# IDP_Shield.net
KiCad netlist of a schematic drawn in EAGLE
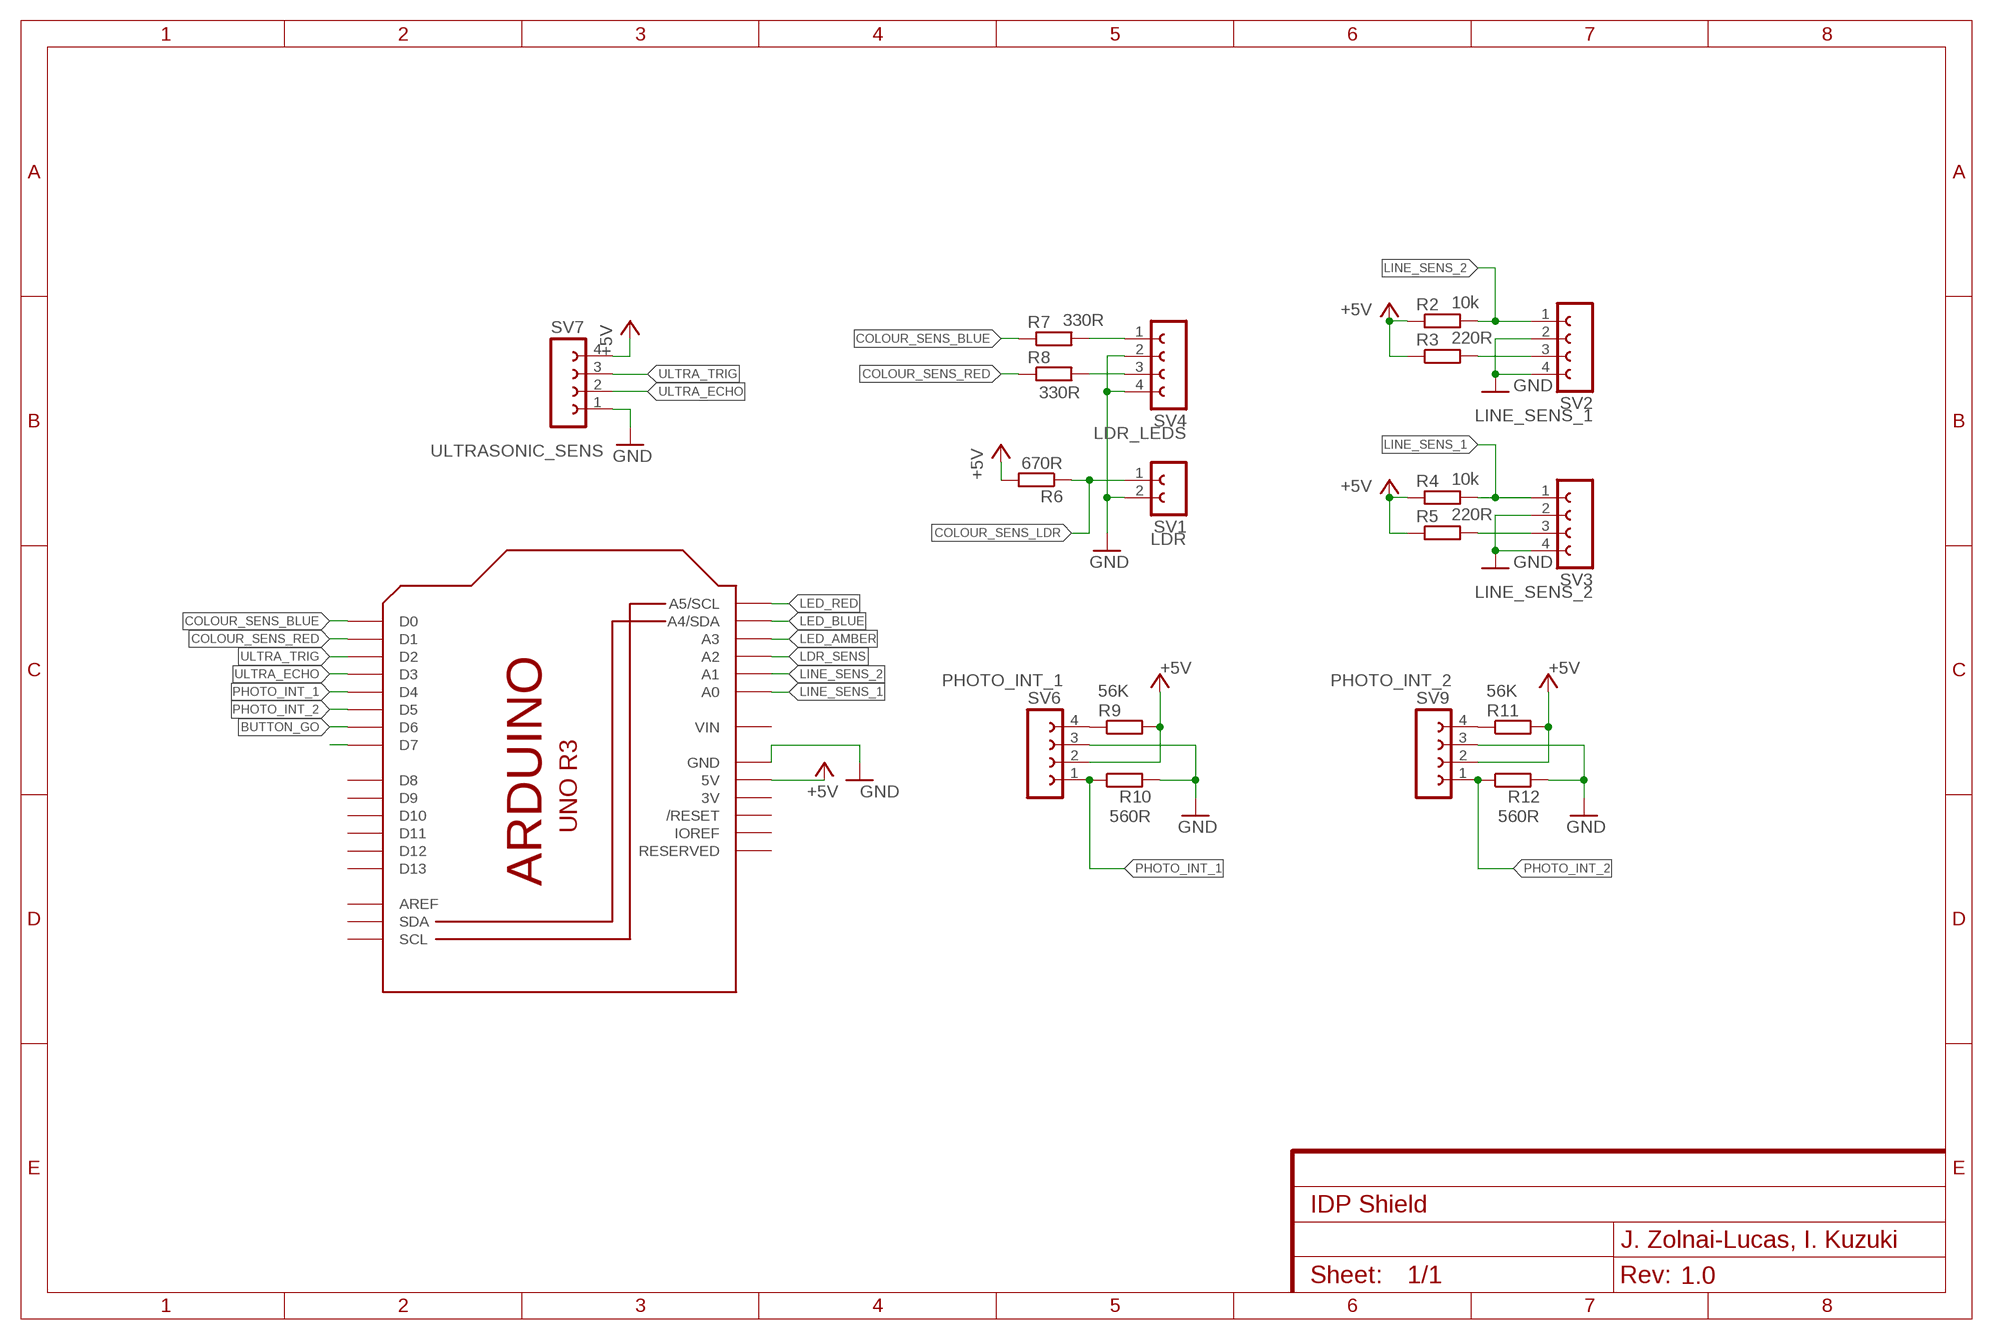
[diagram p0: schematic, sheet 1]

(export (version "E")
  (design (tool "Eeschema 10.0.6"))
  (components
    (comp (ref "M1")
      (value "IDP_PROTOBOARD")
      (footprint "eagle-import:IDP_PROTO")
      (libsource (lib "eagle-import") (part "IDP_PROTOBOARD"))
    )
    (comp (ref "R2")
      (value "10k")
      (footprint "eagle-import:0207_10")
      (libsource (lib "eagle-import") (part "R-EU_0207/10"))
    )
    (comp (ref "R3")
      (value "220R")
      (footprint "eagle-import:0207_10")
      (libsource (lib "eagle-import") (part "R-EU_0207/10"))
    )
    (comp (ref "R4")
      (value "10k")
      (footprint "eagle-import:0207_10")
      (libsource (lib "eagle-import") (part "R-EU_0207/10"))
    )
    (comp (ref "R5")
      (value "220R")
      (footprint "eagle-import:0207_10")
      (libsource (lib "eagle-import") (part "R-EU_0207/10"))
    )
    (comp (ref "R6")
      (value "670R")
      (footprint "eagle-import:0207_10")
      (libsource (lib "eagle-import") (part "R-EU_0207/10"))
    )
    (comp (ref "R7")
      (value "330R")
      (footprint "eagle-import:0207_10")
      (libsource (lib "eagle-import") (part "R-EU_0207/10"))
    )
    (comp (ref "R8")
      (value "330R")
      (footprint "eagle-import:0207_10")
      (libsource (lib "eagle-import") (part "R-EU_0207/10"))
    )
    (comp (ref "R9")
      (value "56K")
      (footprint "eagle-import:0207_10")
      (libsource (lib "eagle-import") (part "R-EU_0207/10"))
    )
    (comp (ref "R10")
      (value "560R")
      (footprint "eagle-import:0207_10")
      (libsource (lib "eagle-import") (part "R-EU_0207/10"))
    )
    (comp (ref "R11")
      (value "56K")
      (footprint "eagle-import:0207_10")
      (libsource (lib "eagle-import") (part "R-EU_0207/10"))
    )
    (comp (ref "R12")
      (value "560R")
      (footprint "eagle-import:0207_10")
      (libsource (lib "eagle-import") (part "R-EU_0207/10"))
    )
    (comp (ref "SV1")
      (value "LDR")
      (footprint "eagle-import:FE02-1")
      (libsource (lib "eagle-import") (part "FE02-1"))
    )
    (comp (ref "SV2")
      (value "LINE_SENS_1")
      (footprint "eagle-import:FE04-1")
      (libsource (lib "eagle-import") (part "FE04-1"))
    )
    (comp (ref "SV3")
      (value "LINE_SENS_2")
      (footprint "eagle-import:FE04-1")
      (libsource (lib "eagle-import") (part "FE04-1"))
    )
    (comp (ref "SV4")
      (value "LDR_LEDS")
      (footprint "eagle-import:FE04-1")
      (libsource (lib "eagle-import") (part "FE04-1"))
    )
    (comp (ref "SV6")
      (value "PHOTO_INT_1")
      (footprint "eagle-import:FE04-1")
      (libsource (lib "eagle-import") (part "FE04-1"))
    )
    (comp (ref "SV7")
      (value "ULTRASONIC_SENS")
      (footprint "eagle-import:FE04-1")
      (libsource (lib "eagle-import") (part "FE04-1"))
    )
    (comp (ref "SV9")
      (value "PHOTO_INT_2")
      (footprint "eagle-import:FE04-1")
      (libsource (lib "eagle-import") (part "FE04-1"))
    )
  )
  (nets
    (net (code "1") (name "+5V") (class "Default")
      (node (ref "M1") (pin "5V") (pinfunction "5V_5V") (pintype "power_in"))
      (node (ref "M1") (pin "5V@0") (pinfunction "5V_5V@0") (pintype "power_in"))
      (node (ref "M1") (pin "5V@1") (pinfunction "5V_5V@1") (pintype "power_in"))
      (node (ref "M1") (pin "5V@10") (pinfunction "5V_5V@10") (pintype "power_in"))
      (node (ref "M1") (pin "5V@11") (pinfunction "5V_5V@11") (pintype "power_in"))
      (node (ref "M1") (pin "5V@12") (pinfunction "5V_5V@12") (pintype "power_in"))
      (node (ref "M1") (pin "5V@13") (pinfunction "5V_5V@13") (pintype "power_in"))
      (node (ref "M1") (pin "5V@14") (pinfunction "5V_5V@14") (pintype "power_in"))
      (node (ref "M1") (pin "5V@15") (pinfunction "5V_5V@15") (pintype "power_in"))
      (node (ref "M1") (pin "5V@16") (pinfunction "5V_5V@16") (pintype "power_in"))
      (node (ref "M1") (pin "5V@17") (pinfunction "5V_5V@17") (pintype "power_in"))
      (node (ref "M1") (pin "5V@18") (pinfunction "5V_5V@18") (pintype "power_in"))
      (node (ref "M1") (pin "5V@19") (pinfunction "5V_5V@19") (pintype "power_in"))
      (node (ref "M1") (pin "5V@2") (pinfunction "5V_5V@2") (pintype "power_in"))
      (node (ref "M1") (pin "5V@20") (pinfunction "5V_5V@20") (pintype "power_in"))
      (node (ref "M1") (pin "5V@21") (pinfunction "5V_5V@21") (pintype "power_in"))
      (node (ref "M1") (pin "5V@22") (pinfunction "5V_5V@22") (pintype "power_in"))
      (node (ref "M1") (pin "5V@23") (pinfunction "5V_5V@23") (pintype "power_in"))
      (node (ref "M1") (pin "5V@24") (pinfunction "5V_5V@24") (pintype "power_in"))
      (node (ref "M1") (pin "5V@25") (pinfunction "5V_5V@25") (pintype "power_in"))
      (node (ref "M1") (pin "5V@26") (pinfunction "5V_5V@26") (pintype "power_in"))
      (node (ref "M1") (pin "5V@27") (pinfunction "5V_5V@27") (pintype "power_in"))
      (node (ref "M1") (pin "5V@28") (pinfunction "5V_5V@28") (pintype "power_in"))
      (node (ref "M1") (pin "5V@29") (pinfunction "5V_5V@29") (pintype "power_in"))
      (node (ref "M1") (pin "5V@3") (pinfunction "5V_5V@3") (pintype "power_in"))
      (node (ref "M1") (pin "5V@30") (pinfunction "5V_5V@30") (pintype "power_in"))
      (node (ref "M1") (pin "5V@31") (pinfunction "5V_5V@31") (pintype "power_in"))
      (node (ref "M1") (pin "5V@32") (pinfunction "5V_5V@32") (pintype "power_in"))
      (node (ref "M1") (pin "5V@33") (pinfunction "5V_5V@33") (pintype "power_in"))
      (node (ref "M1") (pin "5V@34") (pinfunction "5V_5V@34") (pintype "power_in"))
      (node (ref "M1") (pin "5V@35") (pinfunction "5V_5V@35") (pintype "power_in"))
      (node (ref "M1") (pin "5V@36") (pinfunction "5V_5V@36") (pintype "power_in"))
      (node (ref "M1") (pin "5V@37") (pinfunction "5V_5V@37") (pintype "power_in"))
      (node (ref "M1") (pin "5V@38") (pinfunction "5V_5V@38") (pintype "power_in"))
      (node (ref "M1") (pin "5V@39") (pinfunction "5V_5V@39") (pintype "power_in"))
      (node (ref "M1") (pin "5V@4") (pinfunction "5V_5V@4") (pintype "power_in"))
      (node (ref "M1") (pin "5V@40") (pinfunction "5V_5V@40") (pintype "power_in"))
      (node (ref "M1") (pin "5V@5") (pinfunction "5V_5V@5") (pintype "power_in"))
      (node (ref "M1") (pin "5V@6") (pinfunction "5V_5V@6") (pintype "power_in"))
      (node (ref "M1") (pin "5V@7") (pinfunction "5V_5V@7") (pintype "power_in"))
      (node (ref "M1") (pin "5V@8") (pinfunction "5V_5V@8") (pintype "power_in"))
      (node (ref "M1") (pin "5V@9") (pinfunction "5V_5V@9") (pintype "power_in"))
      (node (ref "R11") (pin "2") (pinfunction "2_2") (pintype "passive"))
      (node (ref "R2") (pin "1") (pinfunction "1_1") (pintype "passive"))
      (node (ref "R3") (pin "1") (pinfunction "1_1") (pintype "passive"))
      (node (ref "R4") (pin "1") (pinfunction "1_1") (pintype "passive"))
      (node (ref "R5") (pin "1") (pinfunction "1_1") (pintype "passive"))
      (node (ref "R6") (pin "2") (pinfunction "2_2") (pintype "passive"))
      (node (ref "R9") (pin "2") (pinfunction "2_2") (pintype "passive"))
      (node (ref "SV6") (pin "2") (pinfunction "2_2") (pintype "passive"))
      (node (ref "SV7") (pin "4") (pinfunction "4_4") (pintype "passive"))
      (node (ref "SV9") (pin "2") (pinfunction "2_2") (pintype "passive"))
    )
    (net (code "2") (name "/3V") (class "Default")
      (node (ref "M1") (pin "3V") (pinfunction "3V_3V") (pintype "power_in"))
    )
    (net (code "3") (name "BUTTON_GO") (class "Default")
      (node (ref "M1") (pin "D6") (pinfunction "D6_D6") (pintype "bidirectional"))
    )
    (net (code "4") (name "COLOUR_SENS_BLUE") (class "Default")
      (node (ref "M1") (pin "D0") (pinfunction "D0_D0") (pintype "bidirectional"))
      (node (ref "R7") (pin "1") (pinfunction "1_1") (pintype "passive"))
    )
    (net (code "5") (name "COLOUR_SENS_LDR") (class "Default")
      (node (ref "R6") (pin "1") (pinfunction "1_1") (pintype "passive"))
      (node (ref "SV1") (pin "1") (pinfunction "1_1") (pintype "passive"))
    )
    (net (code "6") (name "COLOUR_SENS_RED") (class "Default")
      (node (ref "M1") (pin "D1") (pinfunction "D1_D1") (pintype "bidirectional"))
      (node (ref "R8") (pin "1") (pinfunction "1_1") (pintype "passive"))
    )
    (net (code "7") (name "GND") (class "Default")
      (node (ref "M1") (pin "GND") (pinfunction "GND_GND") (pintype "power_in"))
      (node (ref "M1") (pin "GND16") (pinfunction "GND_GND16") (pintype "power_in"))
      (node (ref "M1") (pin "GND17") (pinfunction "GND_GND17") (pintype "power_in"))
      (node (ref "M1") (pin "GND18") (pinfunction "GND_GND18") (pintype "power_in"))
      (node (ref "M1") (pin "GND19") (pinfunction "GND_GND19") (pintype "power_in"))
      (node (ref "M1") (pin "GND20") (pinfunction "GND_GND20") (pintype "power_in"))
      (node (ref "M1") (pin "GND21") (pinfunction "GND_GND21") (pintype "power_in"))
      (node (ref "M1") (pin "GND22") (pinfunction "GND_GND22") (pintype "power_in"))
      (node (ref "M1") (pin "GND23") (pinfunction "GND_GND23") (pintype "power_in"))
      (node (ref "M1") (pin "GND24") (pinfunction "GND_GND24") (pintype "power_in"))
      (node (ref "M1") (pin "GND25") (pinfunction "GND_GND25") (pintype "power_in"))
      (node (ref "M1") (pin "GND@1") (pinfunction "GND_GND@1") (pintype "power_in"))
      (node (ref "M1") (pin "GND@10") (pinfunction "GND_GND@10") (pintype "power_in"))
      (node (ref "M1") (pin "GND@11") (pinfunction "GND_GND@11") (pintype "power_in"))
      (node (ref "M1") (pin "GND@12") (pinfunction "GND_GND@12") (pintype "power_in"))
      (node (ref "M1") (pin "GND@13") (pinfunction "GND_GND@13") (pintype "power_in"))
      (node (ref "M1") (pin "GND@14") (pinfunction "GND_GND@14") (pintype "power_in"))
      (node (ref "M1") (pin "GND@15") (pinfunction "GND_GND@15") (pintype "power_in"))
      (node (ref "M1") (pin "GND@2") (pinfunction "GND_GND@2") (pintype "power_in"))
      (node (ref "M1") (pin "GND@26") (pinfunction "GND_GND@26") (pintype "power_in"))
      (node (ref "M1") (pin "GND@27") (pinfunction "GND_GND@27") (pintype "power_in"))
      (node (ref "M1") (pin "GND@28") (pinfunction "GND_GND@28") (pintype "power_in"))
      (node (ref "M1") (pin "GND@29") (pinfunction "GND_GND@29") (pintype "power_in"))
      (node (ref "M1") (pin "GND@3") (pinfunction "GND_GND@3") (pintype "power_in"))
      (node (ref "M1") (pin "GND@30") (pinfunction "GND_GND@30") (pintype "power_in"))
      (node (ref "M1") (pin "GND@31") (pinfunction "GND_GND@31") (pintype "power_in"))
      (node (ref "M1") (pin "GND@32") (pinfunction "GND_GND@32") (pintype "power_in"))
      (node (ref "M1") (pin "GND@33") (pinfunction "GND_GND@33") (pintype "power_in"))
      (node (ref "M1") (pin "GND@34") (pinfunction "GND_GND@34") (pintype "power_in"))
      (node (ref "M1") (pin "GND@35") (pinfunction "GND_GND@35") (pintype "power_in"))
      (node (ref "M1") (pin "GND@36") (pinfunction "GND_GND@36") (pintype "power_in"))
      (node (ref "M1") (pin "GND@37") (pinfunction "GND_GND@37") (pintype "power_in"))
      (node (ref "M1") (pin "GND@38") (pinfunction "GND_GND@38") (pintype "power_in"))
      (node (ref "M1") (pin "GND@39") (pinfunction "GND_GND@39") (pintype "power_in"))
      (node (ref "M1") (pin "GND@4") (pinfunction "GND_GND@4") (pintype "power_in"))
      (node (ref "M1") (pin "GND@40") (pinfunction "GND_GND@40") (pintype "power_in"))
      (node (ref "M1") (pin "GND@41") (pinfunction "GND_GND@41") (pintype "power_in"))
      (node (ref "M1") (pin "GND@42") (pinfunction "GND_GND@42") (pintype "power_in"))
      (node (ref "M1") (pin "GND@43") (pinfunction "GND_GND@43") (pintype "power_in"))
      (node (ref "M1") (pin "GND@44") (pinfunction "GND_GND@44") (pintype "power_in"))
      (node (ref "M1") (pin "GND@45") (pinfunction "GND_GND@45") (pintype "power_in"))
      (node (ref "M1") (pin "GND@46") (pinfunction "GND_GND@46") (pintype "power_in"))
      (node (ref "M1") (pin "GND@47") (pinfunction "GND_GND@47") (pintype "power_in"))
      (node (ref "M1") (pin "GND@48") (pinfunction "GND_GND@48") (pintype "power_in"))
      (node (ref "M1") (pin "GND@5") (pinfunction "GND_GND@5") (pintype "power_in"))
      (node (ref "M1") (pin "GND@6") (pinfunction "GND_GND@6") (pintype "power_in"))
      (node (ref "M1") (pin "GND@7") (pinfunction "GND_GND@7") (pintype "power_in"))
      (node (ref "M1") (pin "GND@8") (pinfunction "GND_GND@8") (pintype "power_in"))
      (node (ref "M1") (pin "GND@9") (pinfunction "GND_GND@9") (pintype "power_in"))
      (node (ref "R10") (pin "2") (pinfunction "2_2") (pintype "passive"))
      (node (ref "R12") (pin "2") (pinfunction "2_2") (pintype "passive"))
      (node (ref "SV1") (pin "2") (pinfunction "2_2") (pintype "passive"))
      (node (ref "SV2") (pin "2") (pinfunction "2_2") (pintype "passive"))
      (node (ref "SV2") (pin "4") (pinfunction "4_4") (pintype "passive"))
      (node (ref "SV3") (pin "2") (pinfunction "2_2") (pintype "passive"))
      (node (ref "SV3") (pin "4") (pinfunction "4_4") (pintype "passive"))
      (node (ref "SV4") (pin "2") (pinfunction "2_2") (pintype "passive"))
      (node (ref "SV4") (pin "4") (pinfunction "4_4") (pintype "passive"))
      (node (ref "SV6") (pin "3") (pinfunction "3_3") (pintype "passive"))
      (node (ref "SV7") (pin "1") (pinfunction "1_1") (pintype "passive"))
      (node (ref "SV9") (pin "3") (pinfunction "3_3") (pintype "passive"))
    )
    (net (code "8") (name "LDR_SENS") (class "Default")
      (node (ref "M1") (pin "A2") (pinfunction "A2_A2") (pintype "bidirectional"))
    )
    (net (code "9") (name "LED_AMBER") (class "Default")
      (node (ref "M1") (pin "A3") (pinfunction "A3_A3") (pintype "bidirectional"))
    )
    (net (code "10") (name "LED_BLUE") (class "Default")
      (node (ref "M1") (pin "A4") (pinfunction "A4/SDA_A4") (pintype "bidirectional"))
    )
    (net (code "11") (name "LED_RED") (class "Default")
      (node (ref "M1") (pin "A5") (pinfunction "A5/SCL_A5") (pintype "bidirectional"))
    )
    (net (code "12") (name "LINE_SENS_1") (class "Default")
      (node (ref "M1") (pin "A0") (pinfunction "A0_A0") (pintype "bidirectional"))
      (node (ref "R4") (pin "2") (pinfunction "2_2") (pintype "passive"))
      (node (ref "SV3") (pin "1") (pinfunction "1_1") (pintype "passive"))
    )
    (net (code "13") (name "LINE_SENS_2") (class "Default")
      (node (ref "M1") (pin "A1") (pinfunction "A1_A1") (pintype "bidirectional"))
      (node (ref "R2") (pin "2") (pinfunction "2_2") (pintype "passive"))
      (node (ref "SV2") (pin "1") (pinfunction "1_1") (pintype "passive"))
    )
    (net (code "14") (name "Net-(R3-Pad2)") (class "Default")
      (node (ref "R3") (pin "2") (pinfunction "2_2") (pintype "passive"))
      (node (ref "SV2") (pin "3") (pinfunction "3_3") (pintype "passive"))
    )
    (net (code "15") (name "Net-(R5-Pad2)") (class "Default")
      (node (ref "R5") (pin "2") (pinfunction "2_2") (pintype "passive"))
      (node (ref "SV3") (pin "3") (pinfunction "3_3") (pintype "passive"))
    )
    (net (code "16") (name "Net-(R7-Pad2)") (class "Default")
      (node (ref "R7") (pin "2") (pinfunction "2_2") (pintype "passive"))
      (node (ref "SV4") (pin "1") (pinfunction "1_1") (pintype "passive"))
    )
    (net (code "17") (name "Net-(R8-Pad2)") (class "Default")
      (node (ref "R8") (pin "2") (pinfunction "2_2") (pintype "passive"))
      (node (ref "SV4") (pin "3") (pinfunction "3_3") (pintype "passive"))
    )
    (net (code "18") (name "Net-(R9-Pad1)") (class "Default")
      (node (ref "R9") (pin "1") (pinfunction "1_1") (pintype "passive"))
      (node (ref "SV6") (pin "4") (pinfunction "4_4") (pintype "passive"))
    )
    (net (code "19") (name "Net-(R11-Pad1)") (class "Default")
      (node (ref "R11") (pin "1") (pinfunction "1_1") (pintype "passive"))
      (node (ref "SV9") (pin "4") (pinfunction "4_4") (pintype "passive"))
    )
    (net (code "20") (name "PHOTO_INT_1") (class "Default")
      (node (ref "M1") (pin "D4") (pinfunction "D4_D4") (pintype "bidirectional"))
      (node (ref "R10") (pin "1") (pinfunction "1_1") (pintype "passive"))
      (node (ref "SV6") (pin "1") (pinfunction "1_1") (pintype "passive"))
    )
    (net (code "21") (name "PHOTO_INT_2") (class "Default")
      (node (ref "M1") (pin "D5") (pinfunction "D5_D5") (pintype "bidirectional"))
      (node (ref "R12") (pin "1") (pinfunction "1_1") (pintype "passive"))
      (node (ref "SV9") (pin "1") (pinfunction "1_1") (pintype "passive"))
    )
    (net (code "22") (name "ULTRA_ECHO") (class "Default")
      (node (ref "M1") (pin "D3") (pinfunction "D3_D3") (pintype "bidirectional"))
      (node (ref "SV7") (pin "2") (pinfunction "2_2") (pintype "passive"))
    )
    (net (code "23") (name "ULTRA_TRIG") (class "Default")
      (node (ref "M1") (pin "D2") (pinfunction "D2_D2") (pintype "bidirectional"))
      (node (ref "SV7") (pin "3") (pinfunction "3_3") (pintype "passive"))
    )
    (net (code "24") (name "unconnected-(M1-PadAREF)") (class "Default")
      (node (ref "M1") (pin "AREF") (pinfunction "AREF_AREF") (pintype "bidirectional"))
    )
    (net (code "25") (name "unconnected-(M1-PadD7)") (class "Default")
      (node (ref "M1") (pin "D7") (pinfunction "D7_D7") (pintype "bidirectional"))
    )
    (net (code "26") (name "unconnected-(M1-PadD8)") (class "Default")
      (node (ref "M1") (pin "D8") (pinfunction "D8_D8") (pintype "bidirectional"))
    )
    (net (code "27") (name "unconnected-(M1-PadD9)") (class "Default")
      (node (ref "M1") (pin "D9") (pinfunction "D9_D9") (pintype "bidirectional"))
    )
    (net (code "28") (name "unconnected-(M1-PadD10)") (class "Default")
      (node (ref "M1") (pin "D10") (pinfunction "D10_D10") (pintype "bidirectional"))
    )
    (net (code "29") (name "unconnected-(M1-PadD11)") (class "Default")
      (node (ref "M1") (pin "D11") (pinfunction "D11_D11") (pintype "bidirectional"))
    )
    (net (code "30") (name "unconnected-(M1-PadD12)") (class "Default")
      (node (ref "M1") (pin "D12") (pinfunction "D12_D12") (pintype "bidirectional"))
    )
    (net (code "31") (name "unconnected-(M1-PadD13)") (class "Default")
      (node (ref "M1") (pin "D13") (pinfunction "D13_D13") (pintype "bidirectional"))
    )
    (net (code "32") (name "unconnected-(M1-PadIOREF)") (class "Default")
      (node (ref "M1") (pin "IOREF") (pinfunction "IOREF_IOREF") (pintype "output"))
    )
    (net (code "33") (name "unconnected-(M1-PadRESERVED)") (class "Default")
      (node (ref "M1") (pin "RESERVED") (pinfunction "RESERVED_RESERVED") (pintype "no_connect"))
    )
    (net (code "34") (name "unconnected-(M1-PadSCL)") (class "Default")
      (node (ref "M1") (pin "SCL") (pinfunction "SCL_SCL") (pintype "bidirectional"))
    )
    (net (code "35") (name "unconnected-(M1-PadSDA)") (class "Default")
      (node (ref "M1") (pin "SDA") (pinfunction "SDA_SDA") (pintype "bidirectional"))
    )
    (net (code "36") (name "unconnected-(M1-PadVIN)") (class "Default")
      (node (ref "M1") (pin "VIN") (pinfunction "VIN_VIN") (pintype "no_connect"))
    )
    (net (code "37") (name "unconnected-(M1-{slash}RESET-PadRESET)") (class "Default")
      (node (ref "M1") (pin "RESET") (pinfunction "/RESET_RESET") (pintype "bidirectional"))
    )
  )
)
